# 1LED_pushdown.net
KiCad netlist of a schematic drawn in EAGLE
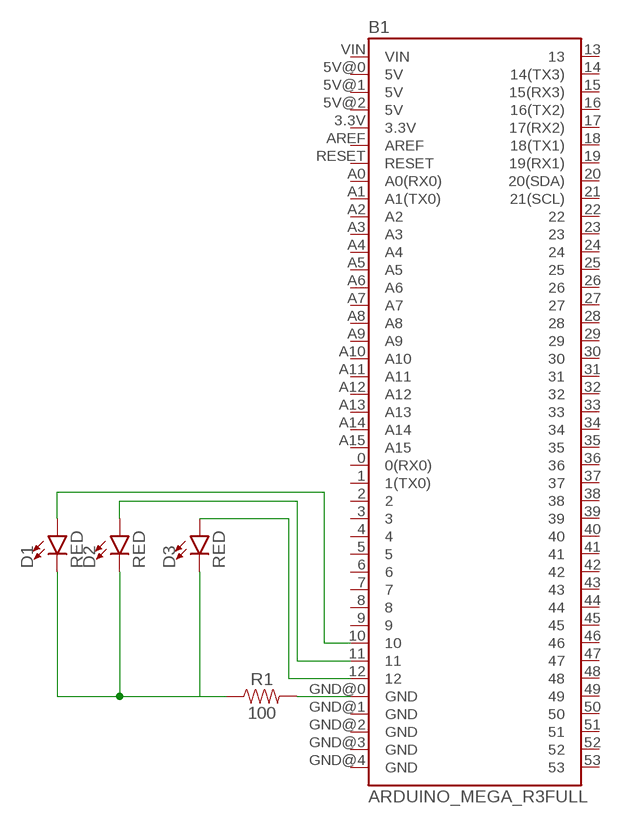
[diagram p0: schematic, sheet 1]

(export (version "E")
  (design (tool "Eeschema 10.0.6"))
  (components
    (comp (ref "B1")
      (value "ARDUINO_MEGA_R3FULL")
      (footprint "eagle-import:ARDUINO_MEGA")
      (libsource (lib "eagle-import") (part "ARDUINO_MEGA_R3FULL"))
    )
    (comp (ref "D1")
      (value "RED")
      (footprint "eagle-import:LED-0603")
      (libsource (lib "eagle-import") (part "LED-RED0603"))
    )
    (comp (ref "D2")
      (value "RED")
      (footprint "eagle-import:LED-0603")
      (libsource (lib "eagle-import") (part "LED-RED0603"))
    )
    (comp (ref "D3")
      (value "RED")
      (footprint "eagle-import:LED-0603")
      (libsource (lib "eagle-import") (part "LED-RED0603"))
    )
    (comp (ref "R1")
      (value "100")
      (footprint "eagle-import:0603")
      (libsource (lib "eagle-import") (part "100OHM-0603-1/4W-5%"))
    )
  )
  (nets
    (net (code "1") (name "Net-(B1-GND-PadGND@0)") (class "Default")
      (node (ref "B1") (pin "GND@0") (pinfunction "GND_GND@0") (pintype "bidirectional"))
      (node (ref "R1") (pin "2") (pinfunction "2_2") (pintype "passive"))
    )
    (net (code "2") (name "Net-(B1-Pad10)") (class "Default")
      (node (ref "B1") (pin "10") (pinfunction "10_10") (pintype "bidirectional"))
      (node (ref "D1") (pin "A") (pinfunction "A_A") (pintype "passive"))
    )
    (net (code "3") (name "Net-(B1-Pad11)") (class "Default")
      (node (ref "B1") (pin "11") (pinfunction "11_11") (pintype "bidirectional"))
      (node (ref "D2") (pin "A") (pinfunction "A_A") (pintype "passive"))
    )
    (net (code "4") (name "Net-(B1-Pad12)") (class "Default")
      (node (ref "B1") (pin "12") (pinfunction "12_12") (pintype "bidirectional"))
      (node (ref "D3") (pin "A") (pinfunction "A_A") (pintype "passive"))
    )
    (net (code "5") (name "Net-(D1-PadC)") (class "Default")
      (node (ref "D1") (pin "C") (pinfunction "C_C") (pintype "passive"))
      (node (ref "D2") (pin "C") (pinfunction "C_C") (pintype "passive"))
      (node (ref "D3") (pin "C") (pinfunction "C_C") (pintype "passive"))
      (node (ref "R1") (pin "1") (pinfunction "1_1") (pintype "passive"))
    )
    (net (code "6") (name "unconnected-(B1-0(RX0)-Pad0)") (class "Default")
      (node (ref "B1") (pin "0") (pinfunction "0(RX0)_0") (pintype "bidirectional"))
    )
    (net (code "7") (name "unconnected-(B1-1(TX0)-Pad1)") (class "Default")
      (node (ref "B1") (pin "1") (pinfunction "1(TX0)_1") (pintype "bidirectional"))
    )
    (net (code "8") (name "unconnected-(B1-5V-Pad5V@0)") (class "Default")
      (node (ref "B1") (pin "5V@0") (pinfunction "5V_5V@0") (pintype "bidirectional"))
    )
    (net (code "9") (name "unconnected-(B1-5V-Pad5V@1)") (class "Default")
      (node (ref "B1") (pin "5V@1") (pinfunction "5V_5V@1") (pintype "bidirectional"))
    )
    (net (code "10") (name "unconnected-(B1-5V-Pad5V@2)") (class "Default")
      (node (ref "B1") (pin "5V@2") (pinfunction "5V_5V@2") (pintype "bidirectional"))
    )
    (net (code "11") (name "unconnected-(B1-14(TX3)-Pad14)") (class "Default")
      (node (ref "B1") (pin "14") (pinfunction "14(TX3)_14") (pintype "bidirectional"))
    )
    (net (code "12") (name "unconnected-(B1-15(RX3)-Pad15)") (class "Default")
      (node (ref "B1") (pin "15") (pinfunction "15(RX3)_15") (pintype "bidirectional"))
    )
    (net (code "13") (name "unconnected-(B1-16(TX2)-Pad16)") (class "Default")
      (node (ref "B1") (pin "16") (pinfunction "16(TX2)_16") (pintype "bidirectional"))
    )
    (net (code "14") (name "unconnected-(B1-17(RX2)-Pad17)") (class "Default")
      (node (ref "B1") (pin "17") (pinfunction "17(RX2)_17") (pintype "bidirectional"))
    )
    (net (code "15") (name "unconnected-(B1-18(TX1)-Pad18)") (class "Default")
      (node (ref "B1") (pin "18") (pinfunction "18(TX1)_18") (pintype "bidirectional"))
    )
    (net (code "16") (name "unconnected-(B1-19(RX1)-Pad19)") (class "Default")
      (node (ref "B1") (pin "19") (pinfunction "19(RX1)_19") (pintype "bidirectional"))
    )
    (net (code "17") (name "unconnected-(B1-20(SDA)-Pad20)") (class "Default")
      (node (ref "B1") (pin "20") (pinfunction "20(SDA)_20") (pintype "bidirectional"))
    )
    (net (code "18") (name "unconnected-(B1-21(SCL)-Pad21)") (class "Default")
      (node (ref "B1") (pin "21") (pinfunction "21(SCL)_21") (pintype "bidirectional"))
    )
    (net (code "19") (name "unconnected-(B1-A0(RX0)-PadA0)") (class "Default")
      (node (ref "B1") (pin "A0") (pinfunction "A0(RX0)_A0") (pintype "bidirectional"))
    )
    (net (code "20") (name "unconnected-(B1-A1(TX0)-PadA1)") (class "Default")
      (node (ref "B1") (pin "A1") (pinfunction "A1(TX0)_A1") (pintype "bidirectional"))
    )
    (net (code "21") (name "unconnected-(B1-GND-PadGND@1)") (class "Default")
      (node (ref "B1") (pin "GND@1") (pinfunction "GND_GND@1") (pintype "bidirectional"))
    )
    (net (code "22") (name "unconnected-(B1-GND-PadGND@2)") (class "Default")
      (node (ref "B1") (pin "GND@2") (pinfunction "GND_GND@2") (pintype "bidirectional"))
    )
    (net (code "23") (name "unconnected-(B1-GND-PadGND@3)") (class "Default")
      (node (ref "B1") (pin "GND@3") (pinfunction "GND_GND@3") (pintype "bidirectional"))
    )
    (net (code "24") (name "unconnected-(B1-GND-PadGND@4)") (class "Default")
      (node (ref "B1") (pin "GND@4") (pinfunction "GND_GND@4") (pintype "bidirectional"))
    )
    (net (code "25") (name "unconnected-(B1-Pad2)") (class "Default")
      (node (ref "B1") (pin "2") (pinfunction "2_2") (pintype "bidirectional"))
    )
    (net (code "26") (name "unconnected-(B1-Pad3)") (class "Default")
      (node (ref "B1") (pin "3") (pinfunction "3_3") (pintype "bidirectional"))
    )
    (net (code "27") (name "unconnected-(B1-Pad3.3V)") (class "Default")
      (node (ref "B1") (pin "3.3V") (pinfunction "3.3V_3.3V") (pintype "bidirectional"))
    )
    (net (code "28") (name "unconnected-(B1-Pad4)") (class "Default")
      (node (ref "B1") (pin "4") (pinfunction "4_4") (pintype "bidirectional"))
    )
    (net (code "29") (name "unconnected-(B1-Pad5)") (class "Default")
      (node (ref "B1") (pin "5") (pinfunction "5_5") (pintype "bidirectional"))
    )
    (net (code "30") (name "unconnected-(B1-Pad6)") (class "Default")
      (node (ref "B1") (pin "6") (pinfunction "6_6") (pintype "bidirectional"))
    )
    (net (code "31") (name "unconnected-(B1-Pad7)") (class "Default")
      (node (ref "B1") (pin "7") (pinfunction "7_7") (pintype "bidirectional"))
    )
    (net (code "32") (name "unconnected-(B1-Pad8)") (class "Default")
      (node (ref "B1") (pin "8") (pinfunction "8_8") (pintype "bidirectional"))
    )
    (net (code "33") (name "unconnected-(B1-Pad9)") (class "Default")
      (node (ref "B1") (pin "9") (pinfunction "9_9") (pintype "bidirectional"))
    )
    (net (code "34") (name "unconnected-(B1-Pad13)") (class "Default")
      (node (ref "B1") (pin "13") (pinfunction "13_13") (pintype "bidirectional"))
    )
    (net (code "35") (name "unconnected-(B1-Pad22)") (class "Default")
      (node (ref "B1") (pin "22") (pinfunction "22_22") (pintype "bidirectional"))
    )
    (net (code "36") (name "unconnected-(B1-Pad23)") (class "Default")
      (node (ref "B1") (pin "23") (pinfunction "23_23") (pintype "bidirectional"))
    )
    (net (code "37") (name "unconnected-(B1-Pad24)") (class "Default")
      (node (ref "B1") (pin "24") (pinfunction "24_24") (pintype "bidirectional"))
    )
    (net (code "38") (name "unconnected-(B1-Pad25)") (class "Default")
      (node (ref "B1") (pin "25") (pinfunction "25_25") (pintype "bidirectional"))
    )
    (net (code "39") (name "unconnected-(B1-Pad26)") (class "Default")
      (node (ref "B1") (pin "26") (pinfunction "26_26") (pintype "bidirectional"))
    )
    (net (code "40") (name "unconnected-(B1-Pad27)") (class "Default")
      (node (ref "B1") (pin "27") (pinfunction "27_27") (pintype "bidirectional"))
    )
    (net (code "41") (name "unconnected-(B1-Pad28)") (class "Default")
      (node (ref "B1") (pin "28") (pinfunction "28_28") (pintype "bidirectional"))
    )
    (net (code "42") (name "unconnected-(B1-Pad29)") (class "Default")
      (node (ref "B1") (pin "29") (pinfunction "29_29") (pintype "bidirectional"))
    )
    (net (code "43") (name "unconnected-(B1-Pad30)") (class "Default")
      (node (ref "B1") (pin "30") (pinfunction "30_30") (pintype "bidirectional"))
    )
    (net (code "44") (name "unconnected-(B1-Pad31)") (class "Default")
      (node (ref "B1") (pin "31") (pinfunction "31_31") (pintype "bidirectional"))
    )
    (net (code "45") (name "unconnected-(B1-Pad32)") (class "Default")
      (node (ref "B1") (pin "32") (pinfunction "32_32") (pintype "bidirectional"))
    )
    (net (code "46") (name "unconnected-(B1-Pad33)") (class "Default")
      (node (ref "B1") (pin "33") (pinfunction "33_33") (pintype "bidirectional"))
    )
    (net (code "47") (name "unconnected-(B1-Pad34)") (class "Default")
      (node (ref "B1") (pin "34") (pinfunction "34_34") (pintype "bidirectional"))
    )
    (net (code "48") (name "unconnected-(B1-Pad35)") (class "Default")
      (node (ref "B1") (pin "35") (pinfunction "35_35") (pintype "bidirectional"))
    )
    (net (code "49") (name "unconnected-(B1-Pad36)") (class "Default")
      (node (ref "B1") (pin "36") (pinfunction "36_36") (pintype "bidirectional"))
    )
    (net (code "50") (name "unconnected-(B1-Pad37)") (class "Default")
      (node (ref "B1") (pin "37") (pinfunction "37_37") (pintype "bidirectional"))
    )
    (net (code "51") (name "unconnected-(B1-Pad38)") (class "Default")
      (node (ref "B1") (pin "38") (pinfunction "38_38") (pintype "bidirectional"))
    )
    (net (code "52") (name "unconnected-(B1-Pad39)") (class "Default")
      (node (ref "B1") (pin "39") (pinfunction "39_39") (pintype "bidirectional"))
    )
    (net (code "53") (name "unconnected-(B1-Pad40)") (class "Default")
      (node (ref "B1") (pin "40") (pinfunction "40_40") (pintype "bidirectional"))
    )
    (net (code "54") (name "unconnected-(B1-Pad41)") (class "Default")
      (node (ref "B1") (pin "41") (pinfunction "41_41") (pintype "bidirectional"))
    )
    (net (code "55") (name "unconnected-(B1-Pad42)") (class "Default")
      (node (ref "B1") (pin "42") (pinfunction "42_42") (pintype "bidirectional"))
    )
    (net (code "56") (name "unconnected-(B1-Pad43)") (class "Default")
      (node (ref "B1") (pin "43") (pinfunction "43_43") (pintype "bidirectional"))
    )
    (net (code "57") (name "unconnected-(B1-Pad44)") (class "Default")
      (node (ref "B1") (pin "44") (pinfunction "44_44") (pintype "bidirectional"))
    )
    (net (code "58") (name "unconnected-(B1-Pad45)") (class "Default")
      (node (ref "B1") (pin "45") (pinfunction "45_45") (pintype "bidirectional"))
    )
    (net (code "59") (name "unconnected-(B1-Pad46)") (class "Default")
      (node (ref "B1") (pin "46") (pinfunction "46_46") (pintype "bidirectional"))
    )
    (net (code "60") (name "unconnected-(B1-Pad47)") (class "Default")
      (node (ref "B1") (pin "47") (pinfunction "47_47") (pintype "bidirectional"))
    )
    (net (code "61") (name "unconnected-(B1-Pad48)") (class "Default")
      (node (ref "B1") (pin "48") (pinfunction "48_48") (pintype "bidirectional"))
    )
    (net (code "62") (name "unconnected-(B1-Pad49)") (class "Default")
      (node (ref "B1") (pin "49") (pinfunction "49_49") (pintype "bidirectional"))
    )
    (net (code "63") (name "unconnected-(B1-Pad50)") (class "Default")
      (node (ref "B1") (pin "50") (pinfunction "50_50") (pintype "bidirectional"))
    )
    (net (code "64") (name "unconnected-(B1-Pad51)") (class "Default")
      (node (ref "B1") (pin "51") (pinfunction "51_51") (pintype "bidirectional"))
    )
    (net (code "65") (name "unconnected-(B1-Pad52)") (class "Default")
      (node (ref "B1") (pin "52") (pinfunction "52_52") (pintype "bidirectional"))
    )
    (net (code "66") (name "unconnected-(B1-Pad53)") (class "Default")
      (node (ref "B1") (pin "53") (pinfunction "53_53") (pintype "bidirectional"))
    )
    (net (code "67") (name "unconnected-(B1-PadA2)") (class "Default")
      (node (ref "B1") (pin "A2") (pinfunction "A2_A2") (pintype "bidirectional"))
    )
    (net (code "68") (name "unconnected-(B1-PadA3)") (class "Default")
      (node (ref "B1") (pin "A3") (pinfunction "A3_A3") (pintype "bidirectional"))
    )
    (net (code "69") (name "unconnected-(B1-PadA4)") (class "Default")
      (node (ref "B1") (pin "A4") (pinfunction "A4_A4") (pintype "bidirectional"))
    )
    (net (code "70") (name "unconnected-(B1-PadA5)") (class "Default")
      (node (ref "B1") (pin "A5") (pinfunction "A5_A5") (pintype "bidirectional"))
    )
    (net (code "71") (name "unconnected-(B1-PadA6)") (class "Default")
      (node (ref "B1") (pin "A6") (pinfunction "A6_A6") (pintype "bidirectional"))
    )
    (net (code "72") (name "unconnected-(B1-PadA7)") (class "Default")
      (node (ref "B1") (pin "A7") (pinfunction "A7_A7") (pintype "bidirectional"))
    )
    (net (code "73") (name "unconnected-(B1-PadA8)") (class "Default")
      (node (ref "B1") (pin "A8") (pinfunction "A8_A8") (pintype "bidirectional"))
    )
    (net (code "74") (name "unconnected-(B1-PadA9)") (class "Default")
      (node (ref "B1") (pin "A9") (pinfunction "A9_A9") (pintype "bidirectional"))
    )
    (net (code "75") (name "unconnected-(B1-PadA10)") (class "Default")
      (node (ref "B1") (pin "A10") (pinfunction "A10_A10") (pintype "bidirectional"))
    )
    (net (code "76") (name "unconnected-(B1-PadA11)") (class "Default")
      (node (ref "B1") (pin "A11") (pinfunction "A11_A11") (pintype "bidirectional"))
    )
    (net (code "77") (name "unconnected-(B1-PadA12)") (class "Default")
      (node (ref "B1") (pin "A12") (pinfunction "A12_A12") (pintype "bidirectional"))
    )
    (net (code "78") (name "unconnected-(B1-PadA13)") (class "Default")
      (node (ref "B1") (pin "A13") (pinfunction "A13_A13") (pintype "bidirectional"))
    )
    (net (code "79") (name "unconnected-(B1-PadA14)") (class "Default")
      (node (ref "B1") (pin "A14") (pinfunction "A14_A14") (pintype "bidirectional"))
    )
    (net (code "80") (name "unconnected-(B1-PadA15)") (class "Default")
      (node (ref "B1") (pin "A15") (pinfunction "A15_A15") (pintype "bidirectional"))
    )
    (net (code "81") (name "unconnected-(B1-PadAREF)") (class "Default")
      (node (ref "B1") (pin "AREF") (pinfunction "AREF_AREF") (pintype "bidirectional"))
    )
    (net (code "82") (name "unconnected-(B1-PadRESET)") (class "Default")
      (node (ref "B1") (pin "RESET") (pinfunction "RESET_RESET") (pintype "bidirectional"))
    )
    (net (code "83") (name "unconnected-(B1-PadVIN)") (class "Default")
      (node (ref "B1") (pin "VIN") (pinfunction "VIN_VIN") (pintype "bidirectional"))
    )
  )
)
